# dip8.net
KiCad netlist of a schematic drawn in EAGLE
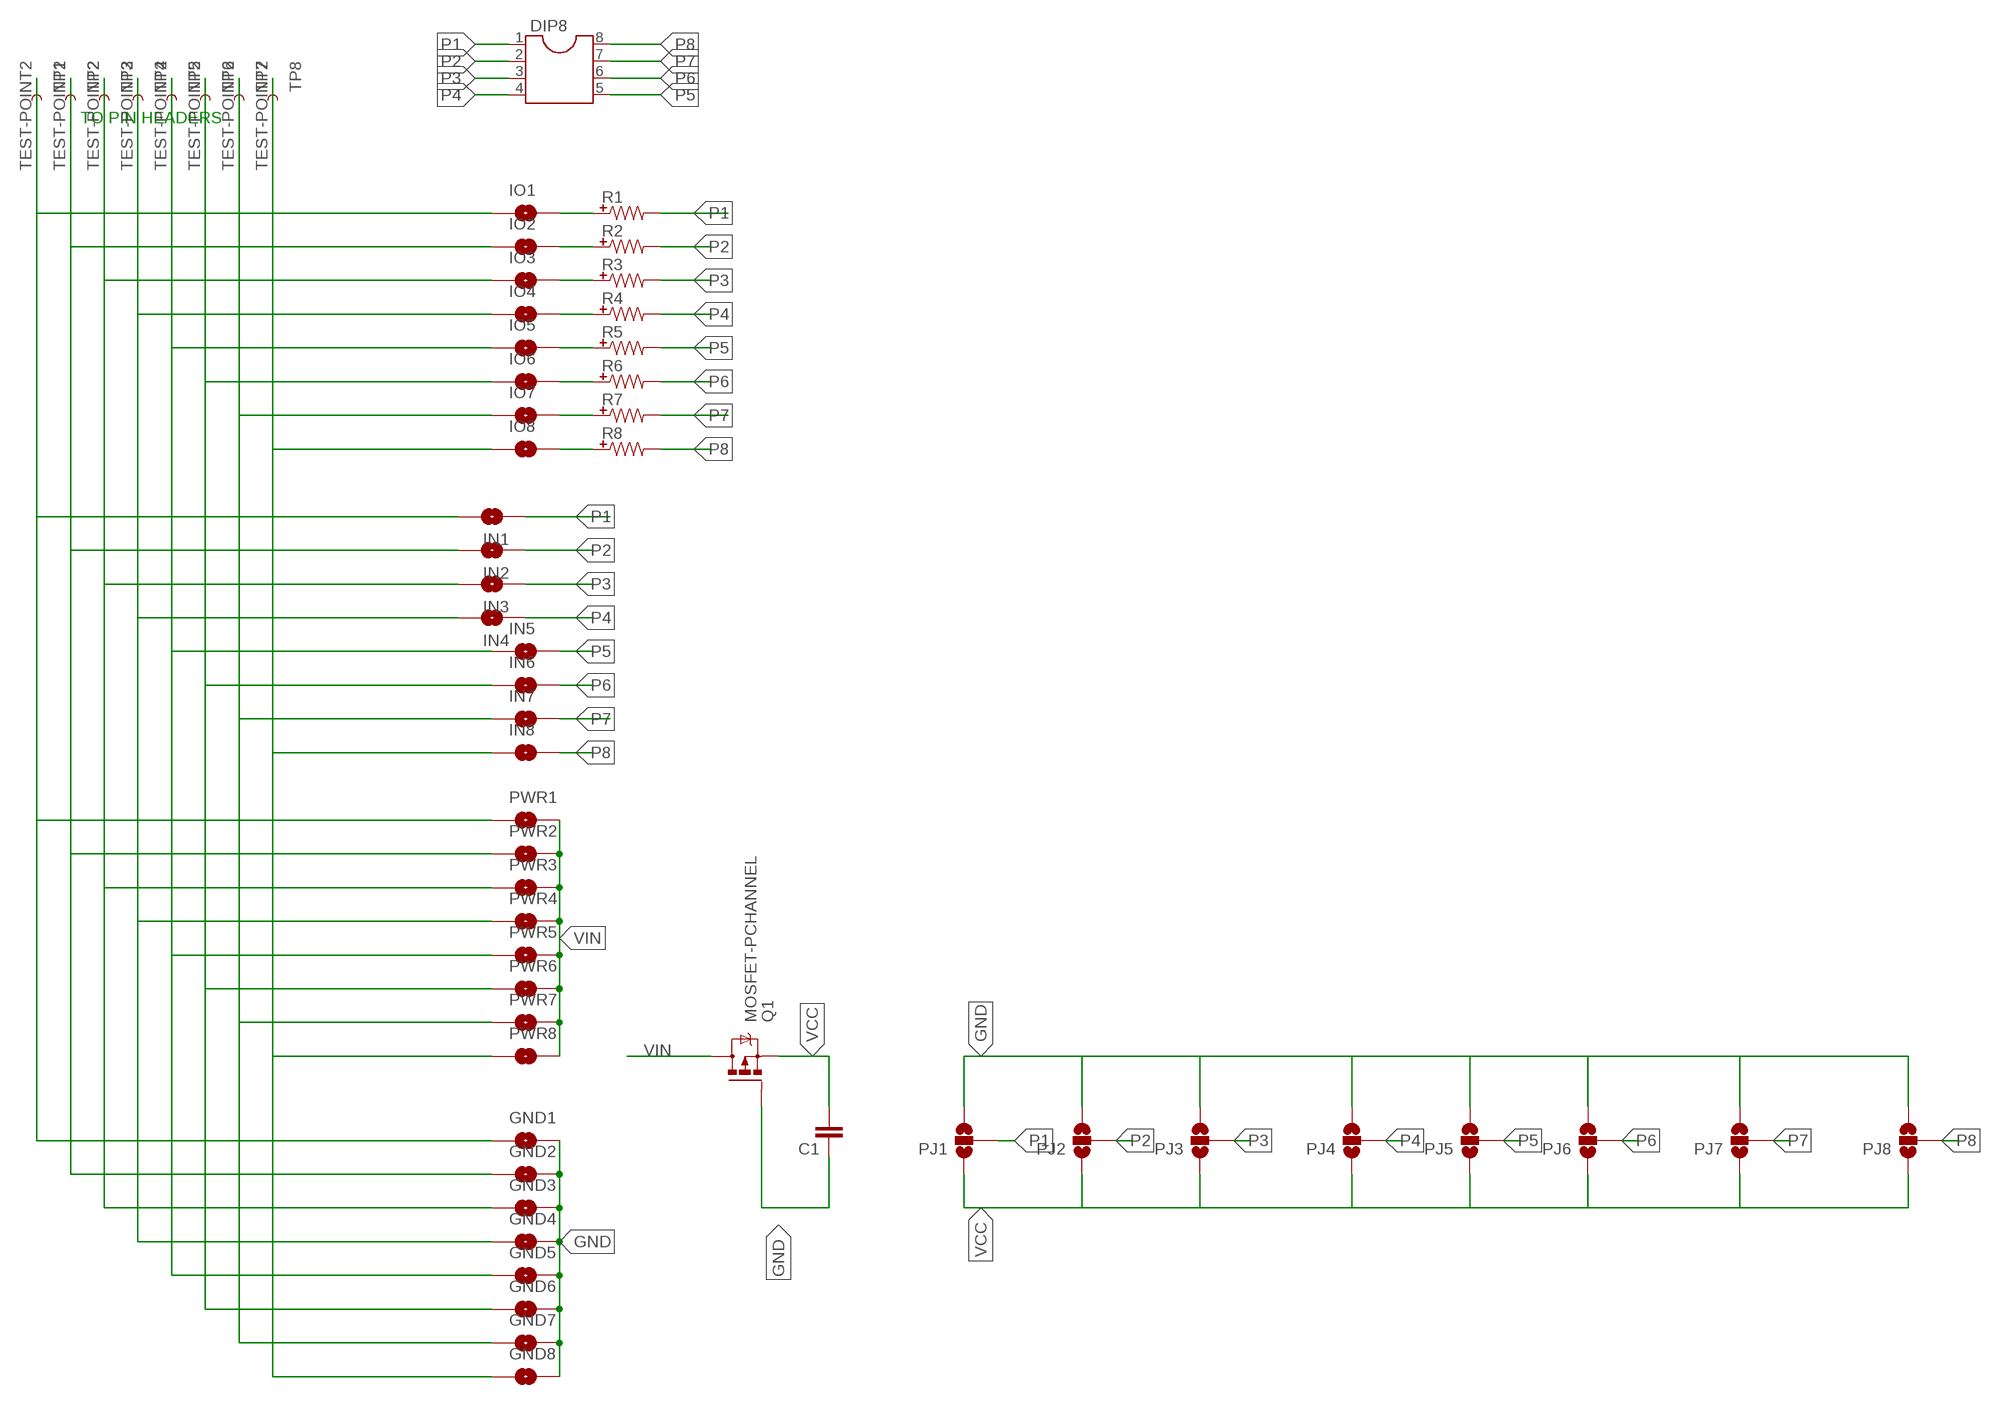
[diagram p0: schematic, sheet 1]

(export (version "E")
  (design (tool "Eeschema 10.0.6"))
  (components
    (comp (ref "C1")
      (value "CAPUNIVERSAL")
      (footprint "eagle-import:0402-0603-0805-UNIVERSAL")
      (libsource (lib "eagle-import") (part "CAPUNIVERSAL"))
    )
    (comp (ref "DIP8")
      (value "DIL8")
      (footprint "eagle-import:DIL08")
      (libsource (lib "eagle-import") (part "DIL8"))
    )
    (comp (ref "GND1")
      (value "SOLDERJUMPERNO")
      (footprint "eagle-import:SJ_2S-NO")
      (libsource (lib "eagle-import") (part "SOLDERJUMPERNO"))
    )
    (comp (ref "GND2")
      (value "SOLDERJUMPERNO")
      (footprint "eagle-import:SJ_2S-NO")
      (libsource (lib "eagle-import") (part "SOLDERJUMPERNO"))
    )
    (comp (ref "GND3")
      (value "SOLDERJUMPERNO")
      (footprint "eagle-import:SJ_2S-NO")
      (libsource (lib "eagle-import") (part "SOLDERJUMPERNO"))
    )
    (comp (ref "GND4")
      (value "SOLDERJUMPERNO")
      (footprint "eagle-import:SJ_2S-NO")
      (libsource (lib "eagle-import") (part "SOLDERJUMPERNO"))
    )
    (comp (ref "GND5")
      (value "SOLDERJUMPERNO")
      (footprint "eagle-import:SJ_2S-NO")
      (libsource (lib "eagle-import") (part "SOLDERJUMPERNO"))
    )
    (comp (ref "GND6")
      (value "SOLDERJUMPERNO")
      (footprint "eagle-import:SJ_2S-NO")
      (libsource (lib "eagle-import") (part "SOLDERJUMPERNO"))
    )
    (comp (ref "GND7")
      (value "SOLDERJUMPERNO")
      (footprint "eagle-import:SJ_2S-NO")
      (libsource (lib "eagle-import") (part "SOLDERJUMPERNO"))
    )
    (comp (ref "GND8")
      (value "SOLDERJUMPERNO")
      (footprint "eagle-import:SJ_2S-NO")
      (libsource (lib "eagle-import") (part "SOLDERJUMPERNO"))
    )
    (comp (ref "IN1")
      (value "SOLDERJUMPERNO")
      (footprint "eagle-import:SJ_2S-NO")
      (libsource (lib "eagle-import") (part "SOLDERJUMPERNO"))
    )
    (comp (ref "IN2")
      (value "SOLDERJUMPERNO")
      (footprint "eagle-import:SJ_2S-NO")
      (libsource (lib "eagle-import") (part "SOLDERJUMPERNO"))
    )
    (comp (ref "IN3")
      (value "SOLDERJUMPERNO")
      (footprint "eagle-import:SJ_2S-NO")
      (libsource (lib "eagle-import") (part "SOLDERJUMPERNO"))
    )
    (comp (ref "IN4")
      (value "SOLDERJUMPERNO")
      (footprint "eagle-import:SJ_2S-NO")
      (libsource (lib "eagle-import") (part "SOLDERJUMPERNO"))
    )
    (comp (ref "IN5")
      (value "SOLDERJUMPERNO")
      (footprint "eagle-import:SJ_2S-NO")
      (libsource (lib "eagle-import") (part "SOLDERJUMPERNO"))
    )
    (comp (ref "IN6")
      (value "SOLDERJUMPERNO")
      (footprint "eagle-import:SJ_2S-NO")
      (libsource (lib "eagle-import") (part "SOLDERJUMPERNO"))
    )
    (comp (ref "IN7")
      (value "SOLDERJUMPERNO")
      (footprint "eagle-import:SJ_2S-NO")
      (libsource (lib "eagle-import") (part "SOLDERJUMPERNO"))
    )
    (comp (ref "IN8")
      (value "SOLDERJUMPERNO")
      (footprint "eagle-import:SJ_2S-NO")
      (libsource (lib "eagle-import") (part "SOLDERJUMPERNO"))
    )
    (comp (ref "IO1")
      (value "SOLDERJUMPERNO")
      (footprint "eagle-import:SJ_2S-NO")
      (libsource (lib "eagle-import") (part "SOLDERJUMPERNO"))
    )
    (comp (ref "IO2")
      (value "SOLDERJUMPERNO")
      (footprint "eagle-import:SJ_2S-NO")
      (libsource (lib "eagle-import") (part "SOLDERJUMPERNO"))
    )
    (comp (ref "IO3")
      (value "SOLDERJUMPERNO")
      (footprint "eagle-import:SJ_2S-NO")
      (libsource (lib "eagle-import") (part "SOLDERJUMPERNO"))
    )
    (comp (ref "IO4")
      (value "SOLDERJUMPERNO")
      (footprint "eagle-import:SJ_2S-NO")
      (libsource (lib "eagle-import") (part "SOLDERJUMPERNO"))
    )
    (comp (ref "IO5")
      (value "SOLDERJUMPERNO")
      (footprint "eagle-import:SJ_2S-NO")
      (libsource (lib "eagle-import") (part "SOLDERJUMPERNO"))
    )
    (comp (ref "IO6")
      (value "SOLDERJUMPERNO")
      (footprint "eagle-import:SJ_2S-NO")
      (libsource (lib "eagle-import") (part "SOLDERJUMPERNO"))
    )
    (comp (ref "IO7")
      (value "SOLDERJUMPERNO")
      (footprint "eagle-import:SJ_2S-NO")
      (libsource (lib "eagle-import") (part "SOLDERJUMPERNO"))
    )
    (comp (ref "IO8")
      (value "SOLDERJUMPERNO")
      (footprint "eagle-import:SJ_2S-NO")
      (libsource (lib "eagle-import") (part "SOLDERJUMPERNO"))
    )
    (comp (ref "PJ1")
      (value "SOLDERJUMPER_2WAYT")
      (footprint "eagle-import:SJ_2")
      (libsource (lib "eagle-import") (part "SOLDERJUMPER_2WAYT"))
    )
    (comp (ref "PJ2")
      (value "SOLDERJUMPER_2WAYT")
      (footprint "eagle-import:SJ_2")
      (libsource (lib "eagle-import") (part "SOLDERJUMPER_2WAYT"))
    )
    (comp (ref "PJ3")
      (value "SOLDERJUMPER_2WAYT")
      (footprint "eagle-import:SJ_2")
      (libsource (lib "eagle-import") (part "SOLDERJUMPER_2WAYT"))
    )
    (comp (ref "PJ4")
      (value "SOLDERJUMPER_2WAYT")
      (footprint "eagle-import:SJ_2")
      (libsource (lib "eagle-import") (part "SOLDERJUMPER_2WAYT"))
    )
    (comp (ref "PJ5")
      (value "SOLDERJUMPER_2WAYT")
      (footprint "eagle-import:SJ_2")
      (libsource (lib "eagle-import") (part "SOLDERJUMPER_2WAYT"))
    )
    (comp (ref "PJ6")
      (value "SOLDERJUMPER_2WAYT")
      (footprint "eagle-import:SJ_2")
      (libsource (lib "eagle-import") (part "SOLDERJUMPER_2WAYT"))
    )
    (comp (ref "PJ7")
      (value "SOLDERJUMPER_2WAYT")
      (footprint "eagle-import:SJ_2")
      (libsource (lib "eagle-import") (part "SOLDERJUMPER_2WAYT"))
    )
    (comp (ref "PJ8")
      (value "SOLDERJUMPER_2WAYT")
      (footprint "eagle-import:SJ_2")
      (libsource (lib "eagle-import") (part "SOLDERJUMPER_2WAYT"))
    )
    (comp (ref "PWR1")
      (value "SOLDERJUMPERNO")
      (footprint "eagle-import:SJ_2S-NO")
      (libsource (lib "eagle-import") (part "SOLDERJUMPERNO"))
    )
    (comp (ref "PWR2")
      (value "SOLDERJUMPERNO")
      (footprint "eagle-import:SJ_2S-NO")
      (libsource (lib "eagle-import") (part "SOLDERJUMPERNO"))
    )
    (comp (ref "PWR3")
      (value "SOLDERJUMPERNO")
      (footprint "eagle-import:SJ_2S-NO")
      (libsource (lib "eagle-import") (part "SOLDERJUMPERNO"))
    )
    (comp (ref "PWR4")
      (value "SOLDERJUMPERNO")
      (footprint "eagle-import:SJ_2S-NO")
      (libsource (lib "eagle-import") (part "SOLDERJUMPERNO"))
    )
    (comp (ref "PWR5")
      (value "SOLDERJUMPERNO")
      (footprint "eagle-import:SJ_2S-NO")
      (libsource (lib "eagle-import") (part "SOLDERJUMPERNO"))
    )
    (comp (ref "PWR6")
      (value "SOLDERJUMPERNO")
      (footprint "eagle-import:SJ_2S-NO")
      (libsource (lib "eagle-import") (part "SOLDERJUMPERNO"))
    )
    (comp (ref "PWR7")
      (value "SOLDERJUMPERNO")
      (footprint "eagle-import:SJ_2S-NO")
      (libsource (lib "eagle-import") (part "SOLDERJUMPERNO"))
    )
    (comp (ref "PWR8")
      (value "SOLDERJUMPERNO")
      (footprint "eagle-import:SJ_2S-NO")
      (libsource (lib "eagle-import") (part "SOLDERJUMPERNO"))
    )
    (comp (ref "Q1")
      (value "MOSFET-PCHANNEL")
      (footprint "eagle-import:SOT23-3")
      (libsource (lib "eagle-import") (part "MOSFET-PCHANNEL"))
    )
    (comp (ref "R1")
      (value "RESISTORUNIVERSAL")
      (footprint "eagle-import:0402-0603-0805-UNIVERSAL")
      (libsource (lib "eagle-import") (part "RESISTORUNIVERSAL"))
    )
    (comp (ref "R2")
      (value "RESISTORUNIVERSAL")
      (footprint "eagle-import:0402-0603-0805-UNIVERSAL")
      (libsource (lib "eagle-import") (part "RESISTORUNIVERSAL"))
    )
    (comp (ref "R3")
      (value "RESISTORUNIVERSAL")
      (footprint "eagle-import:0402-0603-0805-UNIVERSAL")
      (libsource (lib "eagle-import") (part "RESISTORUNIVERSAL"))
    )
    (comp (ref "R4")
      (value "RESISTORUNIVERSAL")
      (footprint "eagle-import:0402-0603-0805-UNIVERSAL")
      (libsource (lib "eagle-import") (part "RESISTORUNIVERSAL"))
    )
    (comp (ref "R5")
      (value "RESISTORUNIVERSAL")
      (footprint "eagle-import:0402-0603-0805-UNIVERSAL")
      (libsource (lib "eagle-import") (part "RESISTORUNIVERSAL"))
    )
    (comp (ref "R6")
      (value "RESISTORUNIVERSAL")
      (footprint "eagle-import:0402-0603-0805-UNIVERSAL")
      (libsource (lib "eagle-import") (part "RESISTORUNIVERSAL"))
    )
    (comp (ref "R7")
      (value "RESISTORUNIVERSAL")
      (footprint "eagle-import:0402-0603-0805-UNIVERSAL")
      (libsource (lib "eagle-import") (part "RESISTORUNIVERSAL"))
    )
    (comp (ref "R8")
      (value "RESISTORUNIVERSAL")
      (footprint "eagle-import:0402-0603-0805-UNIVERSAL")
      (libsource (lib "eagle-import") (part "RESISTORUNIVERSAL"))
    )
    (comp (ref "TP1")
      (value "TEST-POINT2")
      (footprint "eagle-import:PAD.02X.02")
      (libsource (lib "eagle-import") (part "TEST-POINT2"))
    )
    (comp (ref "TP2")
      (value "TEST-POINT2")
      (footprint "eagle-import:PAD.02X.02")
      (libsource (lib "eagle-import") (part "TEST-POINT2"))
    )
    (comp (ref "TP3")
      (value "TEST-POINT2")
      (footprint "eagle-import:PAD.02X.02")
      (libsource (lib "eagle-import") (part "TEST-POINT2"))
    )
    (comp (ref "TP4")
      (value "TEST-POINT2")
      (footprint "eagle-import:PAD.02X.02")
      (libsource (lib "eagle-import") (part "TEST-POINT2"))
    )
    (comp (ref "TP5")
      (value "TEST-POINT2")
      (footprint "eagle-import:PAD.02X.02")
      (libsource (lib "eagle-import") (part "TEST-POINT2"))
    )
    (comp (ref "TP6")
      (value "TEST-POINT2")
      (footprint "eagle-import:PAD.02X.02")
      (libsource (lib "eagle-import") (part "TEST-POINT2"))
    )
    (comp (ref "TP7")
      (value "TEST-POINT2")
      (footprint "eagle-import:PAD.02X.02")
      (libsource (lib "eagle-import") (part "TEST-POINT2"))
    )
    (comp (ref "TP8")
      (value "TEST-POINT2")
      (footprint "eagle-import:PAD.02X.02")
      (libsource (lib "eagle-import") (part "TEST-POINT2"))
    )
  )
  (nets
    (net (code "1") (name "GND") (class "Default")
      (node (ref "C1") (pin "-") (pinfunction "1_-") (pintype "passive"))
      (node (ref "GND1") (pin "2") (pinfunction "2_2") (pintype "passive"))
      (node (ref "GND2") (pin "2") (pinfunction "2_2") (pintype "passive"))
      (node (ref "GND3") (pin "2") (pinfunction "2_2") (pintype "passive"))
      (node (ref "GND4") (pin "2") (pinfunction "2_2") (pintype "passive"))
      (node (ref "GND5") (pin "2") (pinfunction "2_2") (pintype "passive"))
      (node (ref "GND6") (pin "2") (pinfunction "2_2") (pintype "passive"))
      (node (ref "GND7") (pin "2") (pinfunction "2_2") (pintype "passive"))
      (node (ref "GND8") (pin "2") (pinfunction "2_2") (pintype "passive"))
      (node (ref "PJ1") (pin "3") (pinfunction "3_3") (pintype "passive"))
      (node (ref "PJ2") (pin "3") (pinfunction "3_3") (pintype "passive"))
      (node (ref "PJ3") (pin "3") (pinfunction "3_3") (pintype "passive"))
      (node (ref "PJ4") (pin "3") (pinfunction "3_3") (pintype "passive"))
      (node (ref "PJ5") (pin "3") (pinfunction "3_3") (pintype "passive"))
      (node (ref "PJ6") (pin "3") (pinfunction "3_3") (pintype "passive"))
      (node (ref "PJ7") (pin "3") (pinfunction "3_3") (pintype "passive"))
      (node (ref "PJ8") (pin "3") (pinfunction "3_3") (pintype "passive"))
      (node (ref "Q1") (pin "1") (pinfunction "G_1") (pintype "passive"))
    )
    (net (code "2") (name "Net-(R1-1)") (class "Default")
      (node (ref "IO1") (pin "2") (pinfunction "2_2") (pintype "passive"))
      (node (ref "R1") (pin "+") (pinfunction "1_+") (pintype "passive"))
    )
    (net (code "3") (name "Net-(R2-1)") (class "Default")
      (node (ref "IO2") (pin "2") (pinfunction "2_2") (pintype "passive"))
      (node (ref "R2") (pin "+") (pinfunction "1_+") (pintype "passive"))
    )
    (net (code "4") (name "Net-(R3-1)") (class "Default")
      (node (ref "IO3") (pin "2") (pinfunction "2_2") (pintype "passive"))
      (node (ref "R3") (pin "+") (pinfunction "1_+") (pintype "passive"))
    )
    (net (code "5") (name "Net-(R4-1)") (class "Default")
      (node (ref "IO4") (pin "2") (pinfunction "2_2") (pintype "passive"))
      (node (ref "R4") (pin "+") (pinfunction "1_+") (pintype "passive"))
    )
    (net (code "6") (name "Net-(R5-1)") (class "Default")
      (node (ref "IO5") (pin "2") (pinfunction "2_2") (pintype "passive"))
      (node (ref "R5") (pin "+") (pinfunction "1_+") (pintype "passive"))
    )
    (net (code "7") (name "Net-(R6-1)") (class "Default")
      (node (ref "IO6") (pin "2") (pinfunction "2_2") (pintype "passive"))
      (node (ref "R6") (pin "+") (pinfunction "1_+") (pintype "passive"))
    )
    (net (code "8") (name "Net-(R7-1)") (class "Default")
      (node (ref "IO7") (pin "2") (pinfunction "2_2") (pintype "passive"))
      (node (ref "R7") (pin "+") (pinfunction "1_+") (pintype "passive"))
    )
    (net (code "9") (name "Net-(R8-1)") (class "Default")
      (node (ref "IO8") (pin "2") (pinfunction "2_2") (pintype "passive"))
      (node (ref "R8") (pin "+") (pinfunction "1_+") (pintype "passive"))
    )
    (net (code "10") (name "Net-(TP1-1)") (class "Default")
      (node (ref "GND1") (pin "1") (pinfunction "1_1") (pintype "passive"))
      (node (ref "IN1") (pin "2") (pinfunction "2_2") (pintype "passive"))
      (node (ref "IO1") (pin "1") (pinfunction "1_1") (pintype "passive"))
      (node (ref "PWR1") (pin "1") (pinfunction "1_1") (pintype "passive"))
      (node (ref "TP1") (pin "P$1") (pinfunction "1_P$1") (pintype "bidirectional"))
    )
    (net (code "11") (name "Net-(TP2-1)") (class "Default")
      (node (ref "GND2") (pin "1") (pinfunction "1_1") (pintype "passive"))
      (node (ref "IN2") (pin "2") (pinfunction "2_2") (pintype "passive"))
      (node (ref "IO2") (pin "1") (pinfunction "1_1") (pintype "passive"))
      (node (ref "PWR2") (pin "1") (pinfunction "1_1") (pintype "passive"))
      (node (ref "TP2") (pin "P$1") (pinfunction "1_P$1") (pintype "bidirectional"))
    )
    (net (code "12") (name "Net-(TP3-1)") (class "Default")
      (node (ref "GND3") (pin "1") (pinfunction "1_1") (pintype "passive"))
      (node (ref "IN3") (pin "2") (pinfunction "2_2") (pintype "passive"))
      (node (ref "IO3") (pin "1") (pinfunction "1_1") (pintype "passive"))
      (node (ref "PWR3") (pin "1") (pinfunction "1_1") (pintype "passive"))
      (node (ref "TP3") (pin "P$1") (pinfunction "1_P$1") (pintype "bidirectional"))
    )
    (net (code "13") (name "Net-(TP4-1)") (class "Default")
      (node (ref "GND4") (pin "1") (pinfunction "1_1") (pintype "passive"))
      (node (ref "IN4") (pin "2") (pinfunction "2_2") (pintype "passive"))
      (node (ref "IO4") (pin "1") (pinfunction "1_1") (pintype "passive"))
      (node (ref "PWR4") (pin "1") (pinfunction "1_1") (pintype "passive"))
      (node (ref "TP4") (pin "P$1") (pinfunction "1_P$1") (pintype "bidirectional"))
    )
    (net (code "14") (name "Net-(TP5-1)") (class "Default")
      (node (ref "GND5") (pin "1") (pinfunction "1_1") (pintype "passive"))
      (node (ref "IN5") (pin "1") (pinfunction "1_1") (pintype "passive"))
      (node (ref "IO5") (pin "1") (pinfunction "1_1") (pintype "passive"))
      (node (ref "PWR5") (pin "1") (pinfunction "1_1") (pintype "passive"))
      (node (ref "TP5") (pin "P$1") (pinfunction "1_P$1") (pintype "bidirectional"))
    )
    (net (code "15") (name "Net-(TP6-1)") (class "Default")
      (node (ref "GND6") (pin "1") (pinfunction "1_1") (pintype "passive"))
      (node (ref "IN6") (pin "1") (pinfunction "1_1") (pintype "passive"))
      (node (ref "IO6") (pin "1") (pinfunction "1_1") (pintype "passive"))
      (node (ref "PWR6") (pin "1") (pinfunction "1_1") (pintype "passive"))
      (node (ref "TP6") (pin "P$1") (pinfunction "1_P$1") (pintype "bidirectional"))
    )
    (net (code "16") (name "Net-(TP7-1)") (class "Default")
      (node (ref "GND7") (pin "1") (pinfunction "1_1") (pintype "passive"))
      (node (ref "IN7") (pin "1") (pinfunction "1_1") (pintype "passive"))
      (node (ref "IO7") (pin "1") (pinfunction "1_1") (pintype "passive"))
      (node (ref "PWR7") (pin "1") (pinfunction "1_1") (pintype "passive"))
      (node (ref "TP7") (pin "P$1") (pinfunction "1_P$1") (pintype "bidirectional"))
    )
    (net (code "17") (name "Net-(TP8-1)") (class "Default")
      (node (ref "GND8") (pin "1") (pinfunction "1_1") (pintype "passive"))
      (node (ref "IN8") (pin "1") (pinfunction "1_1") (pintype "passive"))
      (node (ref "IO8") (pin "1") (pinfunction "1_1") (pintype "passive"))
      (node (ref "PWR8") (pin "1") (pinfunction "1_1") (pintype "passive"))
      (node (ref "TP8") (pin "P$1") (pinfunction "1_P$1") (pintype "bidirectional"))
    )
    (net (code "18") (name "P1") (class "Default")
      (node (ref "DIP8") (pin "1") (pinfunction "1_1") (pintype "passive"))
      (node (ref "IN1") (pin "1") (pinfunction "1_1") (pintype "passive"))
      (node (ref "PJ1") (pin "2") (pinfunction "2_2") (pintype "passive"))
      (node (ref "R1") (pin "-") (pinfunction "2_-") (pintype "passive"))
    )
    (net (code "19") (name "P2") (class "Default")
      (node (ref "DIP8") (pin "2") (pinfunction "2_2") (pintype "passive"))
      (node (ref "IN2") (pin "1") (pinfunction "1_1") (pintype "passive"))
      (node (ref "PJ2") (pin "2") (pinfunction "2_2") (pintype "passive"))
      (node (ref "R2") (pin "-") (pinfunction "2_-") (pintype "passive"))
    )
    (net (code "20") (name "P3") (class "Default")
      (node (ref "DIP8") (pin "3") (pinfunction "3_3") (pintype "passive"))
      (node (ref "IN3") (pin "1") (pinfunction "1_1") (pintype "passive"))
      (node (ref "PJ3") (pin "2") (pinfunction "2_2") (pintype "passive"))
      (node (ref "R3") (pin "-") (pinfunction "2_-") (pintype "passive"))
    )
    (net (code "21") (name "P4") (class "Default")
      (node (ref "DIP8") (pin "4") (pinfunction "4_4") (pintype "passive"))
      (node (ref "IN4") (pin "1") (pinfunction "1_1") (pintype "passive"))
      (node (ref "PJ4") (pin "2") (pinfunction "2_2") (pintype "passive"))
      (node (ref "R4") (pin "-") (pinfunction "2_-") (pintype "passive"))
    )
    (net (code "22") (name "P5") (class "Default")
      (node (ref "DIP8") (pin "5") (pinfunction "5_5") (pintype "passive"))
      (node (ref "IN5") (pin "2") (pinfunction "2_2") (pintype "passive"))
      (node (ref "PJ5") (pin "2") (pinfunction "2_2") (pintype "passive"))
      (node (ref "R5") (pin "-") (pinfunction "2_-") (pintype "passive"))
    )
    (net (code "23") (name "P6") (class "Default")
      (node (ref "DIP8") (pin "6") (pinfunction "6_6") (pintype "passive"))
      (node (ref "IN6") (pin "2") (pinfunction "2_2") (pintype "passive"))
      (node (ref "PJ6") (pin "2") (pinfunction "2_2") (pintype "passive"))
      (node (ref "R6") (pin "-") (pinfunction "2_-") (pintype "passive"))
    )
    (net (code "24") (name "P7") (class "Default")
      (node (ref "DIP8") (pin "7") (pinfunction "7_7") (pintype "passive"))
      (node (ref "IN7") (pin "2") (pinfunction "2_2") (pintype "passive"))
      (node (ref "PJ7") (pin "2") (pinfunction "2_2") (pintype "passive"))
      (node (ref "R7") (pin "-") (pinfunction "2_-") (pintype "passive"))
    )
    (net (code "25") (name "P8") (class "Default")
      (node (ref "DIP8") (pin "8") (pinfunction "8_8") (pintype "passive"))
      (node (ref "IN8") (pin "2") (pinfunction "2_2") (pintype "passive"))
      (node (ref "PJ8") (pin "2") (pinfunction "2_2") (pintype "passive"))
      (node (ref "R8") (pin "-") (pinfunction "2_-") (pintype "passive"))
    )
    (net (code "26") (name "VCC") (class "Default")
      (node (ref "C1") (pin "+") (pinfunction "2_+") (pintype "passive"))
      (node (ref "PJ1") (pin "1") (pinfunction "1_1") (pintype "passive"))
      (node (ref "PJ2") (pin "1") (pinfunction "1_1") (pintype "passive"))
      (node (ref "PJ3") (pin "1") (pinfunction "1_1") (pintype "passive"))
      (node (ref "PJ4") (pin "1") (pinfunction "1_1") (pintype "passive"))
      (node (ref "PJ5") (pin "1") (pinfunction "1_1") (pintype "passive"))
      (node (ref "PJ6") (pin "1") (pinfunction "1_1") (pintype "passive"))
      (node (ref "PJ7") (pin "1") (pinfunction "1_1") (pintype "passive"))
      (node (ref "PJ8") (pin "1") (pinfunction "1_1") (pintype "passive"))
      (node (ref "Q1") (pin "2") (pinfunction "S_2") (pintype "passive"))
    )
    (net (code "27") (name "VIN") (class "Default")
      (node (ref "PWR1") (pin "2") (pinfunction "2_2") (pintype "passive"))
      (node (ref "PWR2") (pin "2") (pinfunction "2_2") (pintype "passive"))
      (node (ref "PWR3") (pin "2") (pinfunction "2_2") (pintype "passive"))
      (node (ref "PWR4") (pin "2") (pinfunction "2_2") (pintype "passive"))
      (node (ref "PWR5") (pin "2") (pinfunction "2_2") (pintype "passive"))
      (node (ref "PWR6") (pin "2") (pinfunction "2_2") (pintype "passive"))
      (node (ref "PWR7") (pin "2") (pinfunction "2_2") (pintype "passive"))
      (node (ref "PWR8") (pin "2") (pinfunction "2_2") (pintype "passive"))
      (node (ref "Q1") (pin "3") (pinfunction "D_3") (pintype "passive"))
    )
  )
)
